# M0_Express_eh_shield.net
KiCad netlist of a schematic drawn in EAGLE
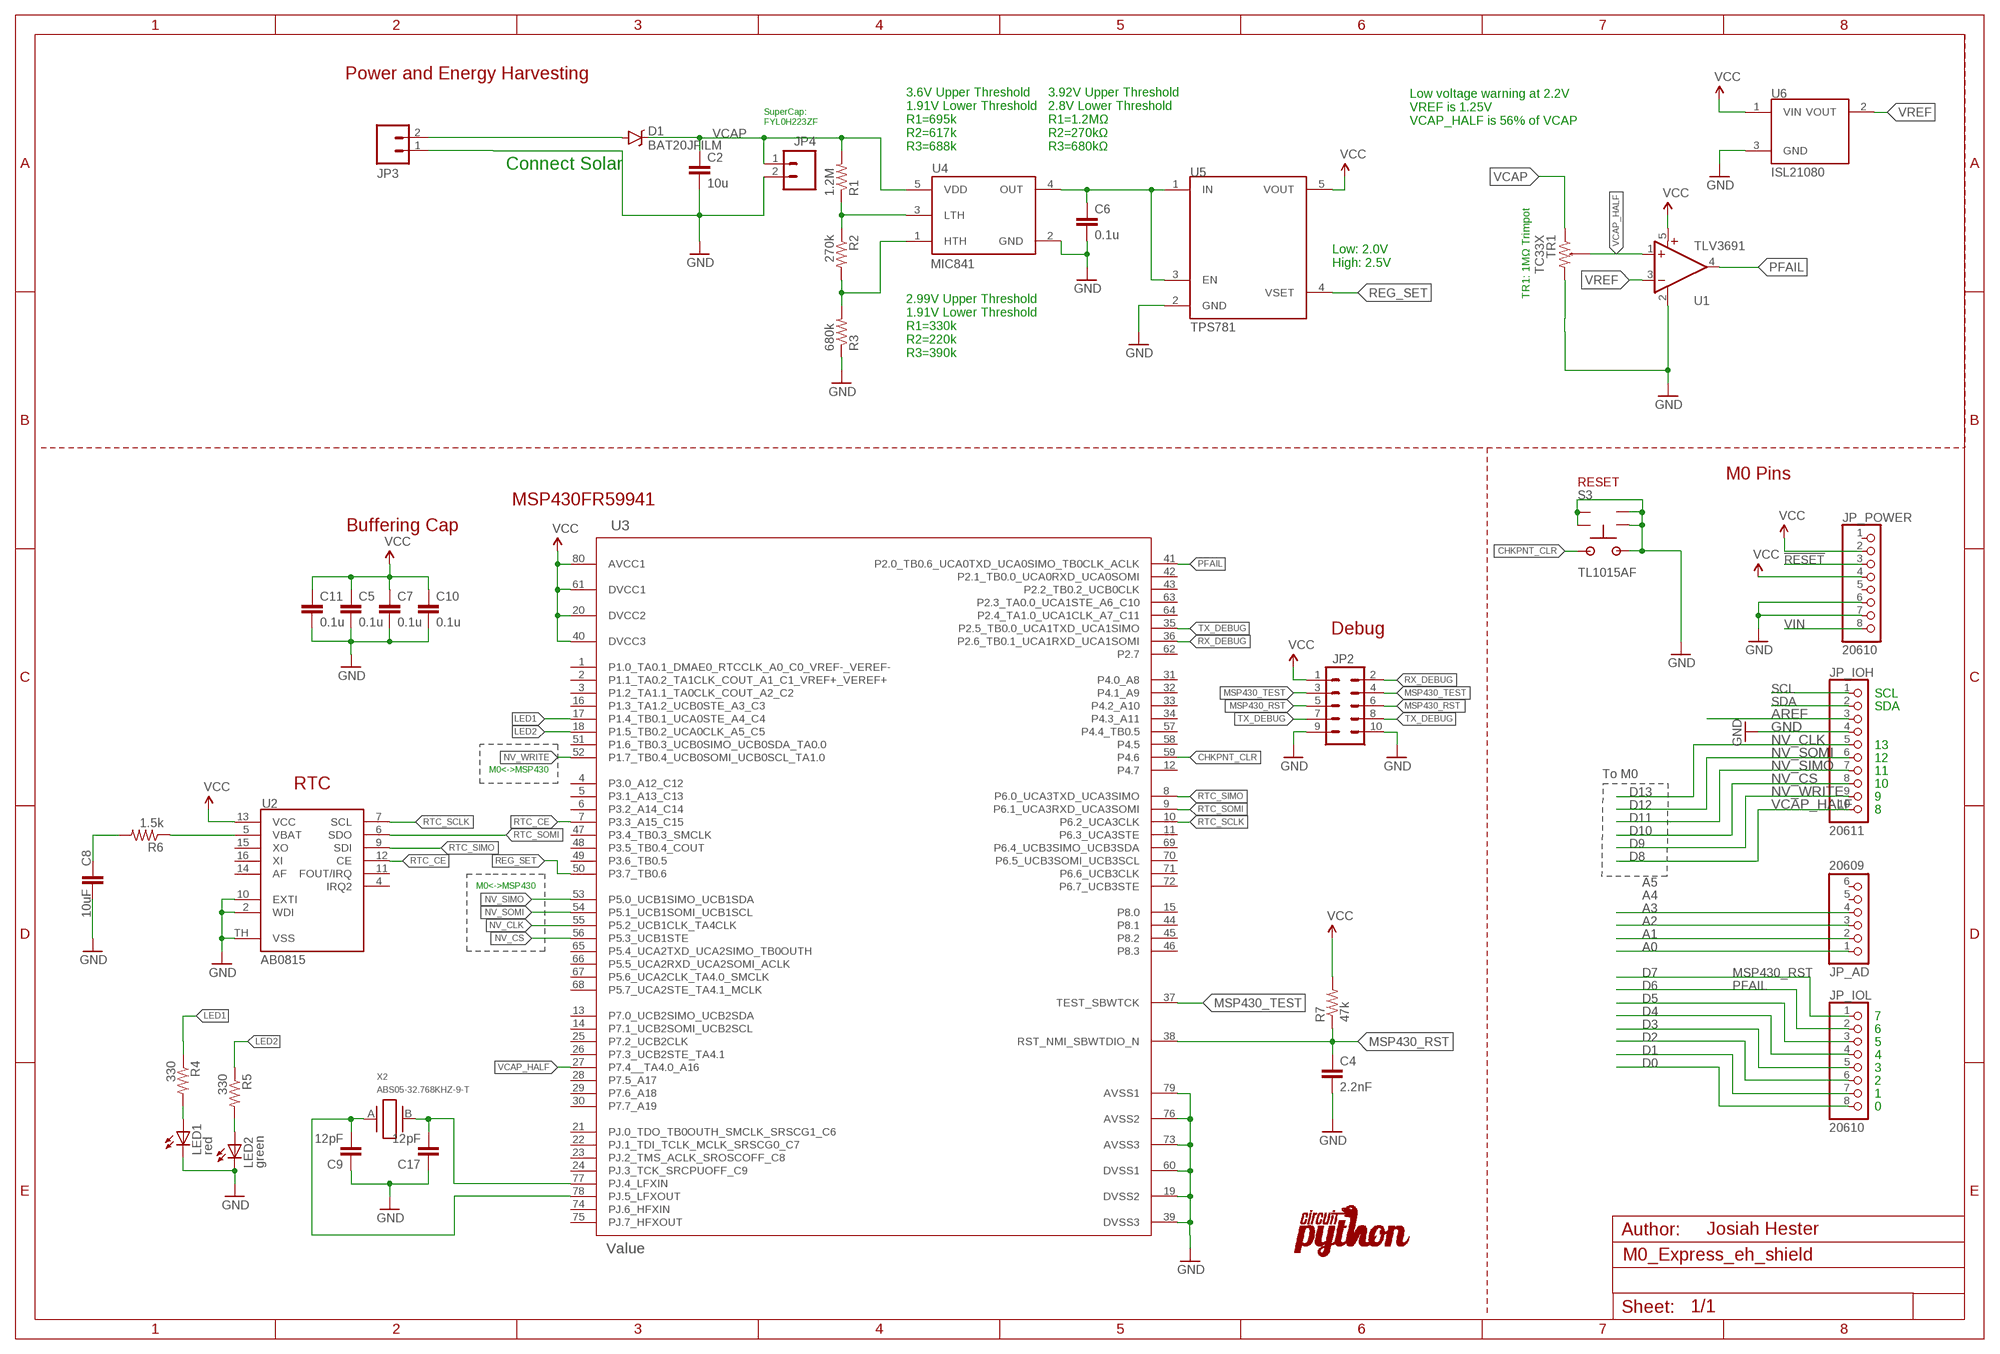
[diagram p0: schematic, sheet 1]

(export (version "E")
  (design (tool "Eeschema 10.0.6"))
  (components
    (comp (ref "C2")
      (value "10u")
      (footprint "eagle-import:0805")
      (libsource (lib "eagle-import") (part "CAP0805"))
    )
    (comp (ref "C4")
      (value "2.2nF")
      (footprint "eagle-import:0603@1")
      (fields (field (name "MPN") "  06035C222KAT2A"))
      (libsource (lib "eagle-import") (part "C-EU0603"))
    )
    (comp (ref "C5")
      (value "0.1u")
      (footprint "eagle-import:0603@1")
      (fields (field (name "MPN") "CL10B104KO8NNNC "))
      (libsource (lib "eagle-import") (part "C-EU0603"))
    )
    (comp (ref "C6")
      (value "0.1u")
      (footprint "eagle-import:0603@1")
      (fields (field (name "MPN") "CL10B104KO8NNNC "))
      (libsource (lib "eagle-import") (part "C-EU0603"))
    )
    (comp (ref "C7")
      (value "0.1u")
      (footprint "eagle-import:0603@1")
      (fields (field (name "MPN") "CL10B104KO8NNNC "))
      (libsource (lib "eagle-import") (part "C-EU0603"))
    )
    (comp (ref "C8")
      (value "10uF")
      (footprint "eagle-import:0805")
      (libsource (lib "eagle-import") (part "CAP0805"))
    )
    (comp (ref "C9")
      (value "12pF")
      (footprint "eagle-import:0603@1")
      (fields (field (name "MPN") "CL10C120JB8NNNC"))
      (libsource (lib "eagle-import") (part "C-EU0603"))
    )
    (comp (ref "C10")
      (value "0.1u")
      (footprint "eagle-import:0603@1")
      (fields (field (name "MPN") "CL10B104KO8NNNC "))
      (libsource (lib "eagle-import") (part "C-EU0603"))
    )
    (comp (ref "C11")
      (value "0.1u")
      (footprint "eagle-import:0603@1")
      (fields (field (name "MPN") "CL10B104KO8NNNC "))
      (libsource (lib "eagle-import") (part "C-EU0603"))
    )
    (comp (ref "C17")
      (value "12pF")
      (footprint "eagle-import:0603@1")
      (fields (field (name "MPN") "CL10C120JB8NNNC"))
      (libsource (lib "eagle-import") (part "C-EU0603"))
    )
    (comp (ref "D1")
      (value "BAT20JFILM")
      (footprint "eagle-import:SOD-323")
      (libsource (lib "eagle-import") (part "BAT20JFILM"))
    )
    (comp (ref "JP2")
      (value "M05X21.27MM")
      (footprint "eagle-import:2X5_1.27MM")
      (fields (field (name "MPN") "3220-10-0100-00 "))
      (libsource (lib "eagle-import") (part "M05X21.27MM"))
    )
    (comp (ref "JP3")
      (value "M025MM")
      (footprint "eagle-import:SCREWTERMINAL-5MM-2")
      (libsource (lib "eagle-import") (part "M025MM"))
    )
    (comp (ref "JP4")
      (value "M025MM")
      (footprint "eagle-import:SCREWTERMINAL-5MM-2")
      (libsource (lib "eagle-import") (part "M025MM"))
    )
    (comp (ref "JP_AD")
      (value "20609")
      (footprint "eagle-import:1X06_OVALWAVE")
      (libsource (lib "eagle-import") (part "HEADER-1X6OVALWAVE"))
    )
    (comp (ref "JP_IOH")
      (value "20611")
      (footprint "eagle-import:1X10_OVALWAVE")
      (libsource (lib "eagle-import") (part "HEADER-1X10OVALWAVE"))
    )
    (comp (ref "JP_IOL")
      (value "20610")
      (footprint "eagle-import:1X08_OVALWAVE")
      (libsource (lib "eagle-import") (part "HEADER-1X8OVALWAVE"))
    )
    (comp (ref "JP_POWER")
      (value "20610")
      (footprint "eagle-import:1X08_OVALWAVE")
      (libsource (lib "eagle-import") (part "HEADER-1X8OVALWAVE"))
    )
    (comp (ref "LED1")
      (value "red")
      (footprint "eagle-import:LED-0603")
      (libsource (lib "eagle-import") (part "LED0603"))
    )
    (comp (ref "LED2")
      (value "green")
      (footprint "eagle-import:LED-0603")
      (libsource (lib "eagle-import") (part "LED0603"))
    )
    (comp (ref "R1")
      (value "1.2M")
      (footprint "eagle-import:0603")
      (fields (field (name "MPN") "RC0603JR-071M2L"))
      (libsource (lib "eagle-import") (part "R-EU0603"))
    )
    (comp (ref "R2")
      (value "270k")
      (footprint "eagle-import:0603")
      (fields (field (name "MPN") "RK73B1JTTD274J"))
      (libsource (lib "eagle-import") (part "R-EU0603"))
    )
    (comp (ref "R3")
      (value "680k")
      (footprint "eagle-import:0603")
      (fields (field (name "MPN") "RMCF0603FT680K"))
      (libsource (lib "eagle-import") (part "R-EU0603"))
    )
    (comp (ref "R4")
      (value "330")
      (footprint "eagle-import:0603")
      (libsource (lib "eagle-import") (part "R-EU0603"))
    )
    (comp (ref "R5")
      (value "330")
      (footprint "eagle-import:0603")
      (libsource (lib "eagle-import") (part "R-EU0603"))
    )
    (comp (ref "R6")
      (value "1.5k")
      (footprint "eagle-import:0603")
      (fields (field (name "MPN") "CRG0603F1K5"))
      (libsource (lib "eagle-import") (part "R-EU0603"))
    )
    (comp (ref "R7")
      (value "47k")
      (footprint "eagle-import:0603")
      (fields (field (name "MPN") "CRCW060347K0JNEAC"))
      (libsource (lib "eagle-import") (part "R-EU0603"))
    )
    (comp (ref "S3")
      (value "TL1015AF")
      (footprint "eagle-import:TS1015")
      (fields (field (name "MPN") "TL1015AF160QG"))
      (libsource (lib "eagle-import") (part "TL1015AF"))
    )
    (comp (ref "TR1")
      (value "TC33X")
      (footprint "eagle-import:TC33X")
      (fields (field (name "MPN") "TC33X-2-105E  "))
      (libsource (lib "eagle-import") (part "TC33X"))
    )
    (comp (ref "U$1")
      (value "LOGO")
      (footprint "eagle-import:CIRCUITPYTHON-LOGO")
      (libsource (lib "eagle-import") (part "LOGO"))
    )
    (comp (ref "U1")
      (value "TLV3691")
      (footprint "eagle-import:SC70-5")
      (fields (field (name "MPN") "TLV3691IDCKR "))
      (libsource (lib "eagle-import") (part "TLV3691"))
    )
    (comp (ref "U2")
      (value "AB0815")
      (footprint "eagle-import:QFN16")
      (fields (field (name "MPN") "AB0815-T3"))
      (libsource (lib "eagle-import") (part "AB0815"))
    )
    (comp (ref "U3")
      (value "Value")
      (footprint "eagle-import:PN0080A_N")
      (fields
        (field (name "MANUFACTURER") "Texas Instruments")
        (field (name "PARTNUMBER") "MSP430FR5994IPNR")
      )
      (libsource (lib "eagle-import") (part "MSP430FR5994IPNR"))
    )
    (comp (ref "U4")
      (value "MIC841")
      (footprint "eagle-import:SC70-5")
      (fields (field (name "MPN") "MIC841HYC5-TR"))
      (libsource (lib "eagle-import") (part "MIC841"))
    )
    (comp (ref "U5")
      (value "TPS781")
      (footprint "eagle-import:DCK_R-PDSO-G5")
      (fields (field (name "MPN") "TPS781250200DDCR"))
      (libsource (lib "eagle-import") (part "TPS781"))
    )
    (comp (ref "U6")
      (value "ISL21080")
      (footprint "eagle-import:SOT-23")
      (fields (field (name "MPN") "ISL21080DIH312Z-TK "))
      (libsource (lib "eagle-import") (part "ISL21080"))
    )
    (comp (ref "X2")
      (value "ABS05-32.768KHZ-9-T")
      (footprint "eagle-import:ABS05")
      (fields (field (name "MPN") "ABS05-32.768KHZ-9-T "))
      (libsource (lib "eagle-import") (part "ABS05-32.768KHZ-9-T"))
    )
  )
  (nets
    (net (code "1") (name "/A0") (class "Default")
      (node (ref "JP_AD") (pin "1") (pinfunction "1_1") (pintype "passive"))
    )
    (net (code "2") (name "/A1") (class "Default")
      (node (ref "JP_AD") (pin "2") (pinfunction "2_2") (pintype "passive"))
    )
    (net (code "3") (name "/A2") (class "Default")
      (node (ref "JP_AD") (pin "3") (pinfunction "3_3") (pintype "passive"))
    )
    (net (code "4") (name "/A3") (class "Default")
      (node (ref "JP_AD") (pin "4") (pinfunction "4_4") (pintype "passive"))
    )
    (net (code "5") (name "/AREF") (class "Default")
      (node (ref "JP_IOH") (pin "3") (pinfunction "3_3") (pintype "passive"))
    )
    (net (code "6") (name "/D0") (class "Default")
      (node (ref "JP_IOL") (pin "8") (pinfunction "8_8") (pintype "passive"))
    )
    (net (code "7") (name "/D1") (class "Default")
      (node (ref "JP_IOL") (pin "7") (pinfunction "7_7") (pintype "passive"))
    )
    (net (code "8") (name "/D2") (class "Default")
      (node (ref "JP_IOL") (pin "6") (pinfunction "6_6") (pintype "passive"))
    )
    (net (code "9") (name "/D3") (class "Default")
      (node (ref "JP_IOL") (pin "5") (pinfunction "5_5") (pintype "passive"))
    )
    (net (code "10") (name "/D4") (class "Default")
      (node (ref "JP_IOL") (pin "4") (pinfunction "4_4") (pintype "passive"))
    )
    (net (code "11") (name "/D5") (class "Default")
      (node (ref "JP_IOL") (pin "3") (pinfunction "3_3") (pintype "passive"))
    )
    (net (code "12") (name "/SCL") (class "Default")
      (node (ref "JP_IOH") (pin "1") (pinfunction "1_1") (pintype "passive"))
    )
    (net (code "13") (name "/SDA") (class "Default")
      (node (ref "JP_IOH") (pin "2") (pinfunction "2_2") (pintype "passive"))
    )
    (net (code "14") (name "/VIN") (class "Default")
      (node (ref "JP_POWER") (pin "8") (pinfunction "8_8") (pintype "passive"))
    )
    (net (code "15") (name "/~{RESET}") (class "Default")
      (node (ref "JP_POWER") (pin "3") (pinfunction "3_3") (pintype "passive"))
    )
    (net (code "16") (name "CHKPNT_CLR") (class "Default")
      (node (ref "S3") (pin "2") (pinfunction "2_2") (pintype "bidirectional"))
      (node (ref "U3") (pin "59") (pinfunction "P4.6_59") (pintype "bidirectional"))
    )
    (net (code "17") (name "GND") (class "Default")
      (node (ref "C10") (pin "2") (pinfunction "2_2") (pintype "passive"))
      (node (ref "C11") (pin "2") (pinfunction "2_2") (pintype "passive"))
      (node (ref "C17") (pin "1") (pinfunction "1_1") (pintype "passive"))
      (node (ref "C2") (pin "2") (pinfunction "2_2") (pintype "passive"))
      (node (ref "C4") (pin "2") (pinfunction "2_2") (pintype "passive"))
      (node (ref "C5") (pin "2") (pinfunction "2_2") (pintype "passive"))
      (node (ref "C6") (pin "2") (pinfunction "2_2") (pintype "passive"))
      (node (ref "C7") (pin "2") (pinfunction "2_2") (pintype "passive"))
      (node (ref "C8") (pin "2") (pinfunction "2_2") (pintype "passive"))
      (node (ref "C9") (pin "1") (pinfunction "1_1") (pintype "passive"))
      (node (ref "JP2") (pin "10") (pinfunction "10_10") (pintype "passive"))
      (node (ref "JP2") (pin "9") (pinfunction "9_9") (pintype "passive"))
      (node (ref "JP3") (pin "1") (pinfunction "1_1") (pintype "passive"))
      (node (ref "JP4") (pin "2") (pinfunction "2_2") (pintype "passive"))
      (node (ref "JP_IOH") (pin "4") (pinfunction "4_4") (pintype "passive"))
      (node (ref "JP_POWER") (pin "6") (pinfunction "6_6") (pintype "passive"))
      (node (ref "JP_POWER") (pin "7") (pinfunction "7_7") (pintype "passive"))
      (node (ref "LED1") (pin "C") (pinfunction "C_C") (pintype "passive"))
      (node (ref "LED2") (pin "C") (pinfunction "C_C") (pintype "passive"))
      (node (ref "R3") (pin "1") (pinfunction "1_1") (pintype "passive"))
      (node (ref "S3") (pin "1") (pinfunction "1_1") (pintype "bidirectional"))
      (node (ref "S3") (pin "G1") (pinfunction "GND_G1") (pintype "bidirectional"))
      (node (ref "S3") (pin "G2") (pinfunction "GND_G2") (pintype "bidirectional"))
      (node (ref "S3") (pin "G3") (pinfunction "GND_G3") (pintype "bidirectional"))
      (node (ref "S3") (pin "G4") (pinfunction "GND_G4") (pintype "bidirectional"))
      (node (ref "TR1") (pin "2") (pinfunction "2_2") (pintype "passive"))
      (node (ref "U1") (pin "2") (pinfunction "GND_2") (pintype "power_in"))
      (node (ref "U2") (pin "10") (pinfunction "EXTI_10") (pintype "bidirectional"))
      (node (ref "U2") (pin "2") (pinfunction "WDI_2") (pintype "bidirectional"))
      (node (ref "U2") (pin "TH") (pinfunction "VSS_TH") (pintype "bidirectional"))
      (node (ref "U3") (pin "19") (pinfunction "DVSS2_19") (pintype "power_in"))
      (node (ref "U3") (pin "39") (pinfunction "DVSS3_39") (pintype "power_in"))
      (node (ref "U3") (pin "60") (pinfunction "DVSS1_60") (pintype "power_in"))
      (node (ref "U3") (pin "73") (pinfunction "AVSS3_73") (pintype "power_in"))
      (node (ref "U3") (pin "76") (pinfunction "AVSS2_76") (pintype "power_in"))
      (node (ref "U3") (pin "79") (pinfunction "AVSS1_79") (pintype "power_in"))
      (node (ref "U4") (pin "2") (pinfunction "GND_2") (pintype "bidirectional"))
      (node (ref "U5") (pin "2") (pinfunction "GND_2") (pintype "bidirectional"))
      (node (ref "U6") (pin "3") (pinfunction "GND_3") (pintype "bidirectional"))
    )
    (net (code "18") (name "LED1") (class "Default")
      (node (ref "R4") (pin "1") (pinfunction "1_1") (pintype "passive"))
      (node (ref "U3") (pin "17") (pinfunction "P1.4_TB0.1_UCA0STE_A4_C4_17") (pintype "bidirectional"))
    )
    (net (code "19") (name "LED2") (class "Default")
      (node (ref "R5") (pin "1") (pinfunction "1_1") (pintype "passive"))
      (node (ref "U3") (pin "18") (pinfunction "P1.5_TB0.2_UCA0CLK_A5_C5_18") (pintype "bidirectional"))
    )
    (net (code "20") (name "MSP430_RST") (class "Default")
      (node (ref "C4") (pin "1") (pinfunction "1_1") (pintype "passive"))
      (node (ref "JP2") (pin "5") (pinfunction "5_5") (pintype "passive"))
      (node (ref "JP2") (pin "6") (pinfunction "6_6") (pintype "passive"))
      (node (ref "JP_IOL") (pin "1") (pinfunction "1_1") (pintype "passive"))
      (node (ref "R7") (pin "1") (pinfunction "1_1") (pintype "passive"))
      (node (ref "U3") (pin "38") (pinfunction "RST_NMI_SBWTDIO_N_38") (pintype "bidirectional"))
    )
    (net (code "21") (name "MSP430_TEST") (class "Default")
      (node (ref "JP2") (pin "3") (pinfunction "3_3") (pintype "passive"))
      (node (ref "JP2") (pin "4") (pinfunction "4_4") (pintype "passive"))
      (node (ref "U3") (pin "37") (pinfunction "TEST_SBWTCK_37") (pintype "input"))
    )
    (net (code "22") (name "NV_CLK") (class "Default")
      (node (ref "JP_IOH") (pin "5") (pinfunction "5_5") (pintype "passive"))
      (node (ref "U3") (pin "55") (pinfunction "P5.2_UCB1CLK_TA4CLK_55") (pintype "bidirectional"))
    )
    (net (code "23") (name "NV_CS") (class "Default")
      (node (ref "JP_IOH") (pin "8") (pinfunction "8_8") (pintype "passive"))
      (node (ref "U3") (pin "56") (pinfunction "P5.3_UCB1STE_56") (pintype "bidirectional"))
    )
    (net (code "24") (name "NV_SIMO") (class "Default")
      (node (ref "JP_IOH") (pin "7") (pinfunction "7_7") (pintype "passive"))
      (node (ref "U3") (pin "53") (pinfunction "P5.0_UCB1SIMO_UCB1SDA_53") (pintype "bidirectional"))
    )
    (net (code "25") (name "NV_SOMI") (class "Default")
      (node (ref "JP_IOH") (pin "6") (pinfunction "6_6") (pintype "passive"))
      (node (ref "U3") (pin "54") (pinfunction "P5.1_UCB1SOMI_UCB1SCL_54") (pintype "bidirectional"))
    )
    (net (code "26") (name "NV_WRITE") (class "Default")
      (node (ref "JP_IOH") (pin "9") (pinfunction "9_9") (pintype "passive"))
      (node (ref "U3") (pin "52") (pinfunction "P1.7_TB0.4_UCB0SOMI_UCB0SCL_TA1.0_52") (pintype "bidirectional"))
    )
    (net (code "27") (name "Net-(C8-Pad1)") (class "Default")
      (node (ref "C8") (pin "1") (pinfunction "1_1") (pintype "passive"))
      (node (ref "R6") (pin "2") (pinfunction "2_2") (pintype "passive"))
    )
    (net (code "28") (name "Net-(D1-PadA)") (class "Default")
      (node (ref "D1") (pin "A") (pinfunction "A_A") (pintype "passive"))
      (node (ref "JP3") (pin "2") (pinfunction "2_2") (pintype "passive"))
    )
    (net (code "29") (name "Net-(LED1-PadA)") (class "Default")
      (node (ref "LED1") (pin "A") (pinfunction "A_A") (pintype "passive"))
      (node (ref "R4") (pin "2") (pinfunction "2_2") (pintype "passive"))
    )
    (net (code "30") (name "Net-(LED2-PadA)") (class "Default")
      (node (ref "LED2") (pin "A") (pinfunction "A_A") (pintype "passive"))
      (node (ref "R5") (pin "2") (pinfunction "2_2") (pintype "passive"))
    )
    (net (code "31") (name "Net-(U2-VBAT)") (class "Default")
      (node (ref "R6") (pin "1") (pinfunction "1_1") (pintype "passive"))
      (node (ref "U2") (pin "5") (pinfunction "VBAT_5") (pintype "bidirectional"))
    )
    (net (code "32") (name "Net-(U3-PJ.4_LFXIN)") (class "Default")
      (node (ref "C17") (pin "2") (pinfunction "2_2") (pintype "passive"))
      (node (ref "U3") (pin "77") (pinfunction "PJ.4_LFXIN_77") (pintype "bidirectional"))
      (node (ref "X2") (pin "B") (pinfunction "2_B") (pintype "bidirectional"))
    )
    (net (code "33") (name "Net-(U3-PJ.5_LFXOUT)") (class "Default")
      (node (ref "C9") (pin "2") (pinfunction "2_2") (pintype "passive"))
      (node (ref "U3") (pin "78") (pinfunction "PJ.5_LFXOUT_78") (pintype "bidirectional"))
      (node (ref "X2") (pin "A") (pinfunction "1_A") (pintype "bidirectional"))
    )
    (net (code "34") (name "Net-(U4-HTH)") (class "Default")
      (node (ref "R2") (pin "2") (pinfunction "2_2") (pintype "passive"))
      (node (ref "R3") (pin "2") (pinfunction "2_2") (pintype "passive"))
      (node (ref "U4") (pin "1") (pinfunction "HTH_1") (pintype "bidirectional"))
    )
    (net (code "35") (name "Net-(U4-LTH)") (class "Default")
      (node (ref "R1") (pin "1") (pinfunction "1_1") (pintype "passive"))
      (node (ref "R2") (pin "1") (pinfunction "1_1") (pintype "passive"))
      (node (ref "U4") (pin "3") (pinfunction "LTH_3") (pintype "bidirectional"))
    )
    (net (code "36") (name "Net-(U4-OUT)") (class "Default")
      (node (ref "C6") (pin "1") (pinfunction "1_1") (pintype "passive"))
      (node (ref "U4") (pin "4") (pinfunction "OUT_4") (pintype "bidirectional"))
      (node (ref "U5") (pin "1") (pinfunction "IN_1") (pintype "bidirectional"))
      (node (ref "U5") (pin "3") (pinfunction "EN_3") (pintype "bidirectional"))
    )
    (net (code "37") (name "PFAIL") (class "Default")
      (node (ref "JP_IOL") (pin "2") (pinfunction "2_2") (pintype "passive"))
      (node (ref "U1") (pin "4") (pinfunction "OUT_4") (pintype "output"))
      (node (ref "U3") (pin "41") (pinfunction "P2.0_TB0.6_UCA0TXD_UCA0SIMO_TB0CLK_ACLK_41") (pintype "bidirectional"))
    )
    (net (code "38") (name "REG_SET") (class "Default")
      (node (ref "U3") (pin "50") (pinfunction "P3.7_TB0.6_50") (pintype "bidirectional"))
      (node (ref "U5") (pin "4") (pinfunction "VSET_4") (pintype "bidirectional"))
    )
    (net (code "39") (name "RTC_CE") (class "Default")
      (node (ref "U2") (pin "12") (pinfunction "CE_12") (pintype "bidirectional"))
      (node (ref "U3") (pin "7") (pinfunction "P3.3_A15_C15_7") (pintype "bidirectional"))
    )
    (net (code "40") (name "RTC_SCLK") (class "Default")
      (node (ref "U2") (pin "7") (pinfunction "SCL_7") (pintype "bidirectional"))
      (node (ref "U3") (pin "10") (pinfunction "P6.2_UCA3CLK_10") (pintype "bidirectional"))
    )
    (net (code "41") (name "RTC_SIMO") (class "Default")
      (node (ref "U2") (pin "9") (pinfunction "SDI_9") (pintype "bidirectional"))
      (node (ref "U3") (pin "8") (pinfunction "P6.0_UCA3TXD_UCA3SIMO_8") (pintype "bidirectional"))
    )
    (net (code "42") (name "RTC_SOMI") (class "Default")
      (node (ref "U2") (pin "6") (pinfunction "SDO_6") (pintype "bidirectional"))
      (node (ref "U3") (pin "9") (pinfunction "P6.1_UCA3RXD_UCA3SOMI_9") (pintype "bidirectional"))
    )
    (net (code "43") (name "RX_DEBUG") (class "Default")
      (node (ref "JP2") (pin "2") (pinfunction "2_2") (pintype "passive"))
      (node (ref "U3") (pin "36") (pinfunction "P2.6_TB0.1_UCA1RXD_UCA1SOMI_36") (pintype "bidirectional"))
    )
    (net (code "44") (name "TX_DEBUG") (class "Default")
      (node (ref "JP2") (pin "7") (pinfunction "7_7") (pintype "passive"))
      (node (ref "JP2") (pin "8") (pinfunction "8_8") (pintype "passive"))
      (node (ref "U3") (pin "35") (pinfunction "P2.5_TB0.0_UCA1TXD_UCA1SIMO_35") (pintype "bidirectional"))
    )
    (net (code "45") (name "VCAP") (class "Default")
      (node (ref "C2") (pin "1") (pinfunction "1_1") (pintype "passive"))
      (node (ref "D1") (pin "C") (pinfunction "C_C") (pintype "passive"))
      (node (ref "JP4") (pin "1") (pinfunction "1_1") (pintype "passive"))
      (node (ref "R1") (pin "2") (pinfunction "2_2") (pintype "passive"))
      (node (ref "TR1") (pin "1") (pinfunction "1_1") (pintype "passive"))
      (node (ref "U4") (pin "5") (pinfunction "VDD_5") (pintype "bidirectional"))
    )
    (net (code "46") (name "VCAP_HALF") (class "Default")
      (node (ref "JP_IOH") (pin "10") (pinfunction "10_10") (pintype "passive"))
      (node (ref "TR1") (pin "W") (pinfunction "W_W") (pintype "bidirectional"))
      (node (ref "U1") (pin "1") (pinfunction "+IN_1") (pintype "input"))
      (node (ref "U3") (pin "27") (pinfunction "P7.4__TA4.0_A16_27") (pintype "bidirectional"))
    )
    (net (code "47") (name "VCC") (class "Default")
      (node (ref "C10") (pin "1") (pinfunction "1_1") (pintype "passive"))
      (node (ref "C11") (pin "1") (pinfunction "1_1") (pintype "passive"))
      (node (ref "C5") (pin "1") (pinfunction "1_1") (pintype "passive"))
      (node (ref "C7") (pin "1") (pinfunction "1_1") (pintype "passive"))
      (node (ref "JP2") (pin "1") (pinfunction "1_1") (pintype "passive"))
      (node (ref "JP_POWER") (pin "2") (pinfunction "2_2") (pintype "passive"))
      (node (ref "JP_POWER") (pin "4") (pinfunction "4_4") (pintype "passive"))
      (node (ref "R7") (pin "2") (pinfunction "2_2") (pintype "passive"))
      (node (ref "U1") (pin "5") (pinfunction "V+_5") (pintype "power_in"))
      (node (ref "U2") (pin "13") (pinfunction "VCC_13") (pintype "bidirectional"))
      (node (ref "U3") (pin "20") (pinfunction "DVCC2_20") (pintype "power_in"))
      (node (ref "U3") (pin "40") (pinfunction "DVCC3_40") (pintype "power_in"))
      (node (ref "U3") (pin "61") (pinfunction "DVCC1_61") (pintype "power_in"))
      (node (ref "U3") (pin "80") (pinfunction "AVCC1_80") (pintype "power_in"))
      (node (ref "U5") (pin "5") (pinfunction "VOUT_5") (pintype "bidirectional"))
      (node (ref "U6") (pin "1") (pinfunction "VIN_1") (pintype "bidirectional"))
    )
    (net (code "48") (name "VREF") (class "Default")
      (node (ref "U1") (pin "3") (pinfunction "-IN_3") (pintype "input"))
      (node (ref "U6") (pin "2") (pinfunction "VOUT_2") (pintype "bidirectional"))
    )
    (net (code "49") (name "unconnected-(JP_AD-Pad5)") (class "Default")
      (node (ref "JP_AD") (pin "5") (pinfunction "5_5") (pintype "passive"))
    )
    (net (code "50") (name "unconnected-(JP_AD-Pad6)") (class "Default")
      (node (ref "JP_AD") (pin "6") (pinfunction "6_6") (pintype "passive"))
    )
    (net (code "51") (name "unconnected-(JP_POWER-Pad1)") (class "Default")
      (node (ref "JP_POWER") (pin "1") (pinfunction "1_1") (pintype "passive"))
    )
    (net (code "52") (name "unconnected-(JP_POWER-Pad5)") (class "Default")
      (node (ref "JP_POWER") (pin "5") (pinfunction "5_5") (pintype "passive"))
    )
    (net (code "53") (name "unconnected-(U2-AF-Pad14)") (class "Default")
      (node (ref "U2") (pin "14") (pinfunction "AF_14") (pintype "bidirectional"))
    )
    (net (code "54") (name "unconnected-(U2-FOUT{slash}IRQ-Pad11)") (class "Default")
      (node (ref "U2") (pin "11") (pinfunction "FOUT/IRQ_11") (pintype "bidirectional"))
    )
    (net (code "55") (name "unconnected-(U2-IRQ2-Pad4)") (class "Default")
      (node (ref "U2") (pin "4") (pinfunction "IRQ2_4") (pintype "bidirectional"))
    )
    (net (code "56") (name "unconnected-(U2-XI-Pad16)") (class "Default")
      (node (ref "U2") (pin "16") (pinfunction "XI_16") (pintype "bidirectional"))
    )
    (net (code "57") (name "unconnected-(U2-XO-Pad15)") (class "Default")
      (node (ref "U2") (pin "15") (pinfunction "XO_15") (pintype "bidirectional"))
    )
    (net (code "58") (name "unconnected-(U3-P1.0_TA0.1_DMAE0_RTCCLK_A0_C0_VREF-_VEREF--Pad1)") (class "Default")
      (node (ref "U3") (pin "1") (pinfunction "P1.0_TA0.1_DMAE0_RTCCLK_A0_C0_VREF-_VEREF-_1") (pintype "bidirectional"))
    )
    (net (code "59") (name "unconnected-(U3-P1.1_TA0.2_TA1CLK_COUT_A1_C1_VREF+_VEREF+-Pad2)") (class "Default")
      (node (ref "U3") (pin "2") (pinfunction "P1.1_TA0.2_TA1CLK_COUT_A1_C1_VREF+_VEREF+_2") (pintype "bidirectional"))
    )
    (net (code "60") (name "unconnected-(U3-P1.2_TA1.1_TA0CLK_COUT_A2_C2-Pad3)") (class "Default")
      (node (ref "U3") (pin "3") (pinfunction "P1.2_TA1.1_TA0CLK_COUT_A2_C2_3") (pintype "bidirectional"))
    )
    (net (code "61") (name "unconnected-(U3-P1.3_TA1.2_UCB0STE_A3_C3-Pad16)") (class "Default")
      (node (ref "U3") (pin "16") (pinfunction "P1.3_TA1.2_UCB0STE_A3_C3_16") (pintype "bidirectional"))
    )
    (net (code "62") (name "unconnected-(U3-P1.6_TB0.3_UCB0SIMO_UCB0SDA_TA0.0-Pad51)") (class "Default")
      (node (ref "U3") (pin "51") (pinfunction "P1.6_TB0.3_UCB0SIMO_UCB0SDA_TA0.0_51") (pintype "bidirectional"))
    )
    (net (code "63") (name "unconnected-(U3-P2.1_TB0.0_UCA0RXD_UCA0SOMI-Pad42)") (class "Default")
      (node (ref "U3") (pin "42") (pinfunction "P2.1_TB0.0_UCA0RXD_UCA0SOMI_42") (pintype "bidirectional"))
    )
    (net (code "64") (name "unconnected-(U3-P2.2_TB0.2_UCB0CLK-Pad43)") (class "Default")
      (node (ref "U3") (pin "43") (pinfunction "P2.2_TB0.2_UCB0CLK_43") (pintype "bidirectional"))
    )
    (net (code "65") (name "unconnected-(U3-P2.3_TA0.0_UCA1STE_A6_C10-Pad63)") (class "Default")
      (node (ref "U3") (pin "63") (pinfunction "P2.3_TA0.0_UCA1STE_A6_C10_63") (pintype "bidirectional"))
    )
    (net (code "66") (name "unconnected-(U3-P2.4_TA1.0_UCA1CLK_A7_C11-Pad64)") (class "Default")
      (node (ref "U3") (pin "64") (pinfunction "P2.4_TA1.0_UCA1CLK_A7_C11_64") (pintype "bidirectional"))
    )
    (net (code "67") (name "unconnected-(U3-P2.7-Pad62)") (class "Default")
      (node (ref "U3") (pin "62") (pinfunction "P2.7_62") (pintype "bidirectional"))
    )
    (net (code "68") (name "unconnected-(U3-P3.0_A12_C12-Pad4)") (class "Default")
      (node (ref "U3") (pin "4") (pinfunction "P3.0_A12_C12_4") (pintype "bidirectional"))
    )
    (net (code "69") (name "unconnected-(U3-P3.1_A13_C13-Pad5)") (class "Default")
      (node (ref "U3") (pin "5") (pinfunction "P3.1_A13_C13_5") (pintype "bidirectional"))
    )
    (net (code "70") (name "unconnected-(U3-P3.2_A14_C14-Pad6)") (class "Default")
      (node (ref "U3") (pin "6") (pinfunction "P3.2_A14_C14_6") (pintype "bidirectional"))
    )
    (net (code "71") (name "unconnected-(U3-P3.4_TB0.3_SMCLK-Pad47)") (class "Default")
      (node (ref "U3") (pin "47") (pinfunction "P3.4_TB0.3_SMCLK_47") (pintype "bidirectional"))
    )
    (net (code "72") (name "unconnected-(U3-P3.5_TB0.4_COUT-Pad48)") (class "Default")
      (node (ref "U3") (pin "48") (pinfunction "P3.5_TB0.4_COUT_48") (pintype "bidirectional"))
    )
    (net (code "73") (name "unconnected-(U3-P3.6_TB0.5-Pad49)") (class "Default")
      (node (ref "U3") (pin "49") (pinfunction "P3.6_TB0.5_49") (pintype "bidirectional"))
    )
    (net (code "74") (name "unconnected-(U3-P4.0_A8-Pad31)") (class "Default")
      (node (ref "U3") (pin "31") (pinfunction "P4.0_A8_31") (pintype "bidirectional"))
    )
    (net (code "75") (name "unconnected-(U3-P4.1_A9-Pad32)") (class "Default")
      (node (ref "U3") (pin "32") (pinfunction "P4.1_A9_32") (pintype "bidirectional"))
    )
    (net (code "76") (name "unconnected-(U3-P4.2_A10-Pad33)") (class "Default")
      (node (ref "U3") (pin "33") (pinfunction "P4.2_A10_33") (pintype "bidirectional"))
    )
    (net (code "77") (name "unconnected-(U3-P4.3_A11-Pad34)") (class "Default")
      (node (ref "U3") (pin "34") (pinfunction "P4.3_A11_34") (pintype "bidirectional"))
    )
    (net (code "78") (name "unconnected-(U3-P4.4_TB0.5-Pad57)") (class "Default")
      (node (ref "U3") (pin "57") (pinfunction "P4.4_TB0.5_57") (pintype "bidirectional"))
    )
    (net (code "79") (name "unconnected-(U3-P4.5-Pad58)") (class "Default")
      (node (ref "U3") (pin "58") (pinfunction "P4.5_58") (pintype "bidirectional"))
    )
    (net (code "80") (name "unconnected-(U3-P4.7-Pad12)") (class "Default")
      (node (ref "U3") (pin "12") (pinfunction "P4.7_12") (pintype "bidirectional"))
    )
    (net (code "81") (name "unconnected-(U3-P5.4_UCA2TXD_UCA2SIMO_TB0OUTH-Pad65)") (class "Default")
      (node (ref "U3") (pin "65") (pinfunction "P5.4_UCA2TXD_UCA2SIMO_TB0OUTH_65") (pintype "bidirectional"))
    )
    (net (code "82") (name "unconnected-(U3-P5.5_UCA2RXD_UCA2SOMI_ACLK-Pad66)") (class "Default")
      (node (ref "U3") (pin "66") (pinfunction "P5.5_UCA2RXD_UCA2SOMI_ACLK_66") (pintype "bidirectional"))
    )
    (net (code "83") (name "unconnected-(U3-P5.6_UCA2CLK_TA4.0_SMCLK-Pad67)") (class "Default")
      (node (ref "U3") (pin "67") (pinfunction "P5.6_UCA2CLK_TA4.0_SMCLK_67") (pintype "bidirectional"))
    )
    (net (code "84") (name "unconnected-(U3-P5.7_UCA2STE_TA4.1_MCLK-Pad68)") (class "Default")
      (node (ref "U3") (pin "68") (pinfunction "P5.7_UCA2STE_TA4.1_MCLK_68") (pintype "bidirectional"))
    )
    (net (code "85") (name "unconnected-(U3-P6.3_UCA3STE-Pad11)") (class "Default")
      (node (ref "U3") (pin "11") (pinfunction "P6.3_UCA3STE_11") (pintype "bidirectional"))
    )
    (net (code "86") (name "unconnected-(U3-P6.4_UCB3SIMO_UCB3SDA-Pad69)") (class "Default")
      (node (ref "U3") (pin "69") (pinfunction "P6.4_UCB3SIMO_UCB3SDA_69") (pintype "bidirectional"))
    )
    (net (code "87") (name "unconnected-(U3-P6.5_UCB3SOMI_UCB3SCL-Pad70)") (class "Default")
      (node (ref "U3") (pin "70") (pinfunction "P6.5_UCB3SOMI_UCB3SCL_70") (pintype "bidirectional"))
    )
    (net (code "88") (name "unconnected-(U3-P6.6_UCB3CLK-Pad71)") (class "Default")
      (node (ref "U3") (pin "71") (pinfunction "P6.6_UCB3CLK_71") (pintype "bidirectional"))
    )
    (net (code "89") (name "unconnected-(U3-P6.7_UCB3STE-Pad72)") (class "Default")
      (node (ref "U3") (pin "72") (pinfunction "P6.7_UCB3STE_72") (pintype "bidirectional"))
    )
    (net (code "90") (name "unconnected-(U3-P7.0_UCB2SIMO_UCB2SDA-Pad13)") (class "Default")
      (node (ref "U3") (pin "13") (pinfunction "P7.0_UCB2SIMO_UCB2SDA_13") (pintype "bidirectional"))
    )
    (net (code "91") (name "unconnected-(U3-P7.1_UCB2SOMI_UCB2SCL-Pad14)") (class "Default")
      (node (ref "U3") (pin "14") (pinfunction "P7.1_UCB2SOMI_UCB2SCL_14") (pintype "bidirectional"))
    )
    (net (code "92") (name "unconnected-(U3-P7.2_UCB2CLK-Pad25)") (class "Default")
      (node (ref "U3") (pin "25") (pinfunction "P7.2_UCB2CLK_25") (pintype "bidirectional"))
    )
    (net (code "93") (name "unconnected-(U3-P7.3_UCB2STE_TA4.1-Pad26)") (class "Default")
      (node (ref "U3") (pin "26") (pinfunction "P7.3_UCB2STE_TA4.1_26") (pintype "bidirectional"))
    )
    (net (code "94") (name "unconnected-(U3-P7.5_A17-Pad28)") (class "Default")
      (node (ref "U3") (pin "28") (pinfunction "P7.5_A17_28") (pintype "bidirectional"))
    )
    (net (code "95") (name "unconnected-(U3-P7.6_A18-Pad29)") (class "Default")
      (node (ref "U3") (pin "29") (pinfunction "P7.6_A18_29") (pintype "bidirectional"))
    )
    (net (code "96") (name "unconnected-(U3-P7.7_A19-Pad30)") (class "Default")
      (node (ref "U3") (pin "30") (pinfunction "P7.7_A19_30") (pintype "bidirectional"))
    )
    (net (code "97") (name "unconnected-(U3-P8.0-Pad15)") (class "Default")
      (node (ref "U3") (pin "15") (pinfunction "P8.0_15") (pintype "bidirectional"))
    )
    (net (code "98") (name "unconnected-(U3-P8.1-Pad44)") (class "Default")
      (node (ref "U3") (pin "44") (pinfunction "P8.1_44") (pintype "bidirectional"))
    )
    (net (code "99") (name "unconnected-(U3-P8.2-Pad45)") (class "Default")
      (node (ref "U3") (pin "45") (pinfunction "P8.2_45") (pintype "bidirectional"))
    )
    (net (code "100") (name "unconnected-(U3-P8.3-Pad46)") (class "Default")
      (node (ref "U3") (pin "46") (pinfunction "P8.3_46") (pintype "bidirectional"))
    )
    (net (code "101") (name "unconnected-(U3-PJ.0_TDO_TB0OUTH_SMCLK_SRSCG1_C6-Pad21)") (class "Default")
      (node (ref "U3") (pin "21") (pinfunction "PJ.0_TDO_TB0OUTH_SMCLK_SRSCG1_C6_21") (pintype "bidirectional"))
    )
    (net (code "102") (name "unconnected-(U3-PJ.1_TDI_TCLK_MCLK_SRSCG0_C7-Pad22)") (class "Default")
      (node (ref "U3") (pin "22") (pinfunction "PJ.1_TDI_TCLK_MCLK_SRSCG0_C7_22") (pintype "bidirectional"))
    )
    (net (code "103") (name "unconnected-(U3-PJ.2_TMS_ACLK_SROSCOFF_C8-Pad23)") (class "Default")
      (node (ref "U3") (pin "23") (pinfunction "PJ.2_TMS_ACLK_SROSCOFF_C8_23") (pintype "bidirectional"))
    )
    (net (code "104") (name "unconnected-(U3-PJ.3_TCK_SRCPUOFF_C9-Pad24)") (class "Default")
      (node (ref "U3") (pin "24") (pinfunction "PJ.3_TCK_SRCPUOFF_C9_24") (pintype "bidirectional"))
    )
    (net (code "105") (name "unconnected-(U3-PJ.6_HFXIN-Pad74)") (class "Default")
      (node (ref "U3") (pin "74") (pinfunction "PJ.6_HFXIN_74") (pintype "bidirectional"))
    )
    (net (code "106") (name "unconnected-(U3-PJ.7_HFXOUT-Pad75)") (class "Default")
      (node (ref "U3") (pin "75") (pinfunction "PJ.7_HFXOUT_75") (pintype "bidirectional"))
    )
  )
)
